# Rails.net
KiCad netlist of a schematic drawn in Altium Designer
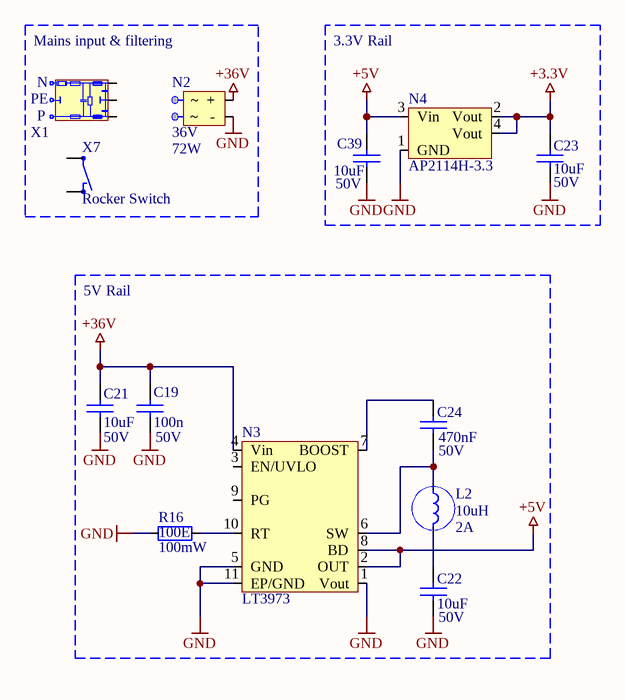
[diagram p0: Rails.SCHDOC]

(export (version "E")
  (design (tool "Eeschema 10.0.6"))
  (components
    (comp (ref "C19")
      (value "100n")
      (footprint "SMD_0603")
      (description "SMD Capacitor")
      (fields (field (name "VALUE2") "50V") (field (name "Comment") "C_SMD_CER_100N_50V_10%_X7R_0603"))
      (libsource (lib "C-Capacitor") (part "C_SMD_CER_100N_50V_10%_X7R_0603"))
    )
    (comp (ref "C21")
      (value "10uF")
      (footprint "SMD_1210")
      (description "SMD Ceramic capacitor")
      (fields (field (name "VALUE2") "50V") (field (name "Comment") "C_SMD_CER_10U_50V_10%_X7R_1210"))
      (libsource (lib "AM") (part "C_SMD_CER_10U_50V_10%_X7R_1210"))
    )
    (comp (ref "C22")
      (value "10uF")
      (footprint "SMD_1210")
      (description "SMD Ceramic capacitor")
      (fields (field (name "VALUE2") "50V") (field (name "Comment") "C_SMD_CER_10U_50V_10%_X7R_1210"))
      (libsource (lib "AM") (part "C_SMD_CER_10U_50V_10%_X7R_1210"))
    )
    (comp (ref "C23")
      (value "10uF")
      (footprint "SMD_1210")
      (description "SMD Ceramic capacitor")
      (fields (field (name "VALUE2") "50V") (field (name "Comment") "C_SMD_CER_10U_50V_10%_X7R_1210"))
      (libsource (lib "AM") (part "C_SMD_CER_10U_50V_10%_X7R_1210"))
    )
    (comp (ref "C24")
      (value "470nF")
      (footprint "SMD_0603")
      (fields (field (name "VALUE2") "50V") (field (name "Comment") "C_SMD_CER_470N_50V_10%_X7R_0603"))
      (libsource (lib "AM") (part "C_SMD_CER_470N_50V_10%_X7R_0603"))
    )
    (comp (ref "C39")
      (value "10uF")
      (footprint "SMD_1210")
      (description "SMD Ceramic capacitor")
      (fields (field (name "VALUE2") "50V") (field (name "Comment") "C_SMD_CER_10U_50V_10%_X7R_1210"))
      (libsource (lib "AM") (part "C_SMD_CER_10U_50V_10%_X7R_1210"))
    )
    (comp (ref "L2")
      (value "10uH")
      (footprint "SMD_INDUCT_74477710")
      (description "SMD Inductor")
      (fields (field (name "VALUE2") "2A") (field (name "Comment") "L_SMD_10U_2A_20%_IND_74477710"))
      (libsource (lib "AM") (part "L_SMD_10U_2A_20%_IND_74477710"))
    )
    (comp (ref "N2")
      (value "36V")
      (footprint "THT_CON_P2.54_D0.9_1X2")
      (fields (field (name "VALUE2") "72W") (field (name "Comment") "N_EXT_ACDC_36V_75W"))
      (libsource (lib "AM") (part "N_EXT_ACDC_36V_75W"))
    )
    (comp (ref "N3")
      (value "N_LT3973-5_DFN-10")
      (footprint "SMD_DFN_10_3X3")
      (description "42V, 750mA Step-Down Regulator with 2.5uA Quiescent Current and Integrated Diodes")
      (fields (field (name "TYPE") "LT3973"))
      (libsource (lib "N-Analog") (part "N_LT3973-5_DFN-10-3x3"))
    )
    (comp (ref "N4")
      (value "N_AP2114H-3.3_SOT223")
      (footprint "SMD_SOT_22_3")
      (description "1A Low Noise CMOS LDO Regulator")
      (fields (field (name "TYPE") "AP2114H-3.3"))
      (libsource (lib "N-Analog") (part "N_AP2114H-3.3_SOT223"))
    )
    (comp (ref "R16")
      (value "100E")
      (footprint "SMD_0603")
      (description "SMD Resistor")
      (fields
        (field (name "VALUE2") "100mW")
        (field (name "Comment") "R_SMD_THINFILM_100E_0W1_1%_50PPM_0603")
      )
      (libsource (lib "R-Resistor") (part "R_SMD_THINFILM_100E_0W1_1%_50PPM_0603"))
    )
    (comp (ref "X1")
      (value "X_POWER_ENTRY_MODULE_W/FILTER_W/FUSE_10A_SMD_CONNECTOR")
      (footprint "SMD_CON_P5.08_W2.0_L5.0_1X3")
      (description "MOD POWER ENTRY INLET WITH FUSE 10A")
      (libsource (lib "AM") (part "X_POWER_ENTRY_MODULE_W/FILTER_W/FUSE_10A_SMD_CONNECTOR"))
    )
    (comp (ref "X7")
      (value "X_SWITCH_ROCKER_SPST_6A_250VAC")
      (footprint "THT_CON_P5.08_D1.5_1X2")
      (fields (field (name "TYPE") "Rocker Switch"))
      (libsource (lib "X-Connectors") (part "X_SWITCH_ROCKER_SPST_6A_250VAC"))
    )
  )
  (nets
    (net (code "1") (name "+3.3V") (class "Default")
      (node (ref "C23") (pin "2") (pinfunction "2_2") (pintype "passive"))
      (node (ref "N4") (pin "2") (pinfunction "Vout_2") (pintype "passive"))
      (node (ref "N4") (pin "4") (pinfunction "Vout_4") (pintype "passive"))
    )
    (net (code "2") (name "+5V") (class "Default")
      (node (ref "C39") (pin "2") (pinfunction "2_2") (pintype "passive"))
      (node (ref "N3") (pin "2") (pinfunction "OUT_2") (pintype "passive"))
      (node (ref "N3") (pin "8") (pinfunction "BD_8") (pintype "passive"))
      (node (ref "N4") (pin "3") (pinfunction "Vin_3") (pintype "passive"))
    )
    (net (code "3") (name "+36V") (class "Default")
      (node (ref "C19") (pin "2") (pinfunction "2_2") (pintype "passive"))
      (node (ref "C21") (pin "2") (pinfunction "2_2") (pintype "passive"))
      (node (ref "N2") (pin "1") (pinfunction "~__+_1") (pintype "passive"))
      (node (ref "N3") (pin "4") (pinfunction "Vin_4") (pintype "passive"))
    )
    (net (code "4") (name "GND") (class "Default")
      (node (ref "C19") (pin "1") (pinfunction "1_1") (pintype "passive"))
      (node (ref "C21") (pin "1") (pinfunction "1_1") (pintype "passive"))
      (node (ref "C22") (pin "1") (pinfunction "1_1") (pintype "passive"))
      (node (ref "C23") (pin "1") (pinfunction "1_1") (pintype "passive"))
      (node (ref "C39") (pin "1") (pinfunction "1_1") (pintype "passive"))
      (node (ref "N2") (pin "2") (pinfunction "~___-_2") (pintype "passive"))
      (node (ref "N3") (pin "1") (pinfunction "Vout_1") (pintype "passive"))
      (node (ref "N3") (pin "11") (pinfunction "EP/GND_11") (pintype "passive"))
      (node (ref "N3") (pin "5") (pinfunction "GND_5") (pintype "passive"))
      (node (ref "N4") (pin "1") (pinfunction "GND_1") (pintype "passive"))
      (node (ref "R16") (pin "1") (pinfunction "1_1") (pintype "passive"))
    )
    (net (code "5") (name "Net-(C22-Pad2)") (class "Default")
      (node (ref "C22") (pin "2") (pinfunction "2_2") (pintype "passive"))
      (node (ref "L2") (pin "2") (pinfunction "2_2") (pintype "passive"))
    )
    (net (code "6") (name "Net-(N3-BOOST)") (class "Default")
      (node (ref "C24") (pin "2") (pinfunction "2_2") (pintype "passive"))
      (node (ref "N3") (pin "7") (pinfunction "BOOST_7") (pintype "passive"))
    )
    (net (code "7") (name "Net-(N3-RT)") (class "Default")
      (node (ref "N3") (pin "10") (pinfunction "RT_10") (pintype "passive"))
      (node (ref "R16") (pin "2") (pinfunction "2_2") (pintype "passive"))
    )
    (net (code "8") (name "Net-(N3-SW)") (class "Default")
      (node (ref "C24") (pin "1") (pinfunction "1_1") (pintype "passive"))
      (node (ref "L2") (pin "1") (pinfunction "1_1") (pintype "passive"))
      (node (ref "N3") (pin "6") (pinfunction "SW_6") (pintype "passive"))
    )
    (net (code "9") (name "unconnected-(N3-EN{slash}UVLO-Pad3)") (class "Default")
      (node (ref "N3") (pin "3") (pinfunction "EN/UVLO_3") (pintype "passive"))
    )
    (net (code "10") (name "unconnected-(N3-PG-Pad9)") (class "Default")
      (node (ref "N3") (pin "9") (pinfunction "PG_9") (pintype "passive"))
    )
    (net (code "11") (name "unconnected-(X1-Pad1)") (class "Default")
      (node (ref "X1") (pin "1") (pinfunction "1_1") (pintype "passive"))
    )
    (net (code "12") (name "unconnected-(X1-Pad2)") (class "Default")
      (node (ref "X1") (pin "2") (pinfunction "2_2") (pintype "passive"))
    )
    (net (code "13") (name "unconnected-(X1-Pad3)") (class "Default")
      (node (ref "X1") (pin "3") (pinfunction "3_3") (pintype "passive"))
    )
    (net (code "14") (name "unconnected-(X7-Pad1)") (class "Default")
      (node (ref "X7") (pin "1") (pinfunction "1_1") (pintype "passive"))
    )
    (net (code "15") (name "unconnected-(X7-Pad2)") (class "Default")
      (node (ref "X7") (pin "2") (pinfunction "2_2") (pintype "passive"))
    )
  )
)
